# exp1_1_1.net
KiCad netlist of a schematic drawn in EAGLE
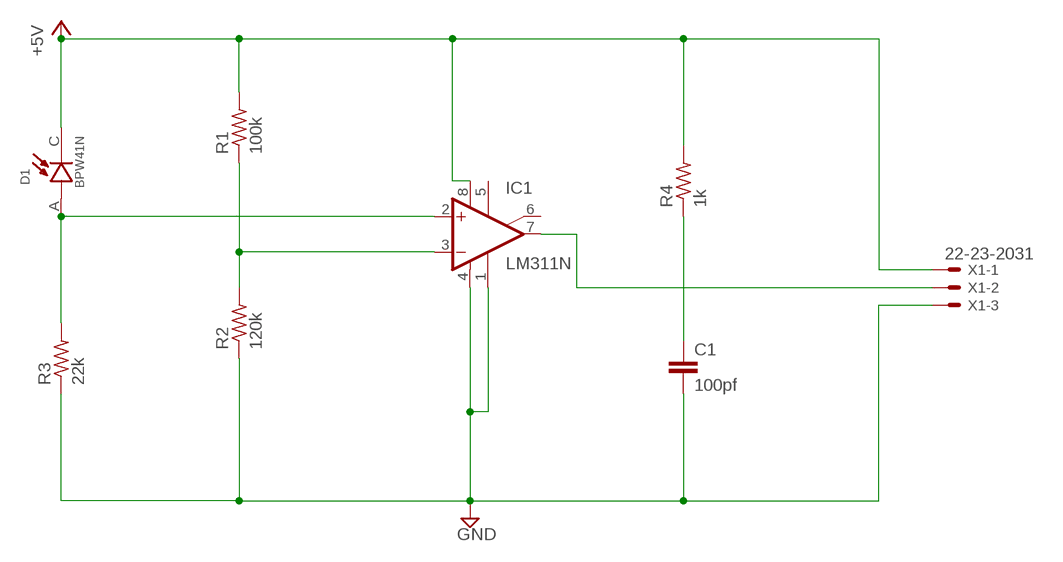
[diagram p0: schematic, sheet 1]

(export (version "E")
  (design (tool "Eeschema 10.0.6"))
  (components
    (comp (ref "C1")
      (value "100pf")
      (footprint "eagle-import:C2.5-3")
      (libsource (lib "eagle-import") (part "C2,5-3"))
    )
    (comp (ref "D1")
      (value "BPW41N")
      (footprint "eagle-import:DIO_BPW41N")
      (fields (field (name "MF") "Vishay Semiconductor Opto Division"))
      (libsource (lib "eagle-import") (part "BPW41N"))
    )
    (comp (ref "IC1")
      (value "LM311N")
      (footprint "eagle-import:DIL08")
      (libsource (lib "eagle-import") (part "LM311N"))
    )
    (comp (ref "R1")
      (value "100k")
      (footprint "eagle-import:0207_10")
      (libsource (lib "eagle-import") (part "R-US_0207/10"))
    )
    (comp (ref "R2")
      (value "120k")
      (footprint "eagle-import:0207_10")
      (libsource (lib "eagle-import") (part "R-US_0207/10"))
    )
    (comp (ref "R3")
      (value "22k")
      (footprint "eagle-import:0207_10")
      (libsource (lib "eagle-import") (part "R-US_0207/10"))
    )
    (comp (ref "R4")
      (value "1k")
      (footprint "eagle-import:0207_10")
      (libsource (lib "eagle-import") (part "R-US_0207/10"))
    )
    (comp (ref "X1")
      (value "22-23-2031")
      (footprint "eagle-import:22-23-2031")
      (fields (field (name "MF") "MOLEX"))
      (libsource (lib "eagle-import") (part "22-23-2031"))
    )
  )
  (nets
    (net (code "1") (name "+5V") (class "Default")
      (node (ref "D1") (pin "C") (pinfunction "C_C") (pintype "passive"))
      (node (ref "IC1") (pin "8") (pinfunction "V+_8") (pintype "power_in"))
      (node (ref "R1") (pin "2") (pinfunction "2_2") (pintype "passive"))
      (node (ref "R4") (pin "2") (pinfunction "2_2") (pintype "passive"))
      (node (ref "X1") (pin "1") (pinfunction "S_1") (pintype "passive"))
    )
    (net (code "2") (name "GND") (class "Default")
      (node (ref "C1") (pin "2") (pinfunction "2_2") (pintype "passive"))
      (node (ref "IC1") (pin "1") (pinfunction "GND_1") (pintype "passive"))
      (node (ref "IC1") (pin "4") (pinfunction "V-_4") (pintype "power_in"))
      (node (ref "R2") (pin "1") (pinfunction "1_1") (pintype "passive"))
      (node (ref "R3") (pin "1") (pinfunction "1_1") (pintype "passive"))
      (node (ref "X1") (pin "3") (pinfunction "S_3") (pintype "passive"))
    )
    (net (code "3") (name "Net-(C1-Pad1)") (class "Default")
      (node (ref "C1") (pin "1") (pinfunction "1_1") (pintype "passive"))
      (node (ref "R4") (pin "1") (pinfunction "1_1") (pintype "passive"))
    )
    (net (code "4") (name "Net-(IC1-+IN)") (class "Default")
      (node (ref "D1") (pin "A") (pinfunction "A_A") (pintype "passive"))
      (node (ref "IC1") (pin "2") (pinfunction "+IN_2") (pintype "input"))
      (node (ref "R3") (pin "2") (pinfunction "2_2") (pintype "passive"))
    )
    (net (code "5") (name "Net-(IC1--IN)") (class "Default")
      (node (ref "IC1") (pin "3") (pinfunction "-IN_3") (pintype "input"))
      (node (ref "R1") (pin "1") (pinfunction "1_1") (pintype "passive"))
      (node (ref "R2") (pin "2") (pinfunction "2_2") (pintype "passive"))
    )
    (net (code "6") (name "Net-(IC1-OUT)") (class "Default")
      (node (ref "IC1") (pin "7") (pinfunction "OUT_7") (pintype "output"))
      (node (ref "X1") (pin "2") (pinfunction "S_2") (pintype "passive"))
    )
    (net (code "7") (name "unconnected-(IC1-ON-Pad5)") (class "Default")
      (node (ref "IC1") (pin "5") (pinfunction "ON_5") (pintype "passive"))
    )
    (net (code "8") (name "unconnected-(IC1-ON{slash}STR-Pad6)") (class "Default")
      (node (ref "IC1") (pin "6") (pinfunction "ON/STR_6") (pintype "passive"))
    )
  )
)
